# mainboard.net
KiCad netlist of a schematic drawn in EAGLE
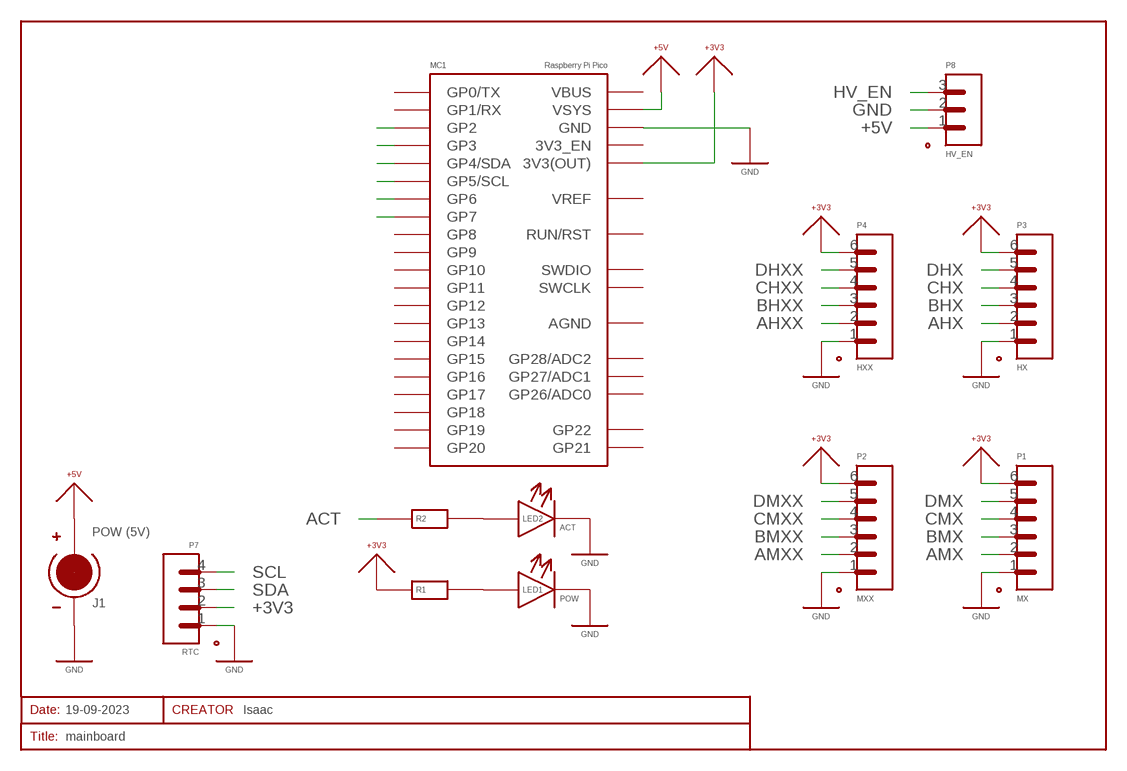
[diagram p0: schematic, sheet 1]

(export (version "E")
  (design (tool "Eeschema 10.0.6"))
  (components
    (comp (ref "CREATOR")
      (value "Isaac")
      (footprint "eagle-import:INFO_T")
      (libsource (lib "eagle-import") (part "INFO_T"))
    )
    (comp (ref "J1")
      (value "POW (5V)")
      (footprint "eagle-import:XH2.54_2-PIN")
      (libsource (lib "eagle-import") (part "DC_POWER_CENTER-POS_XH2.54"))
    )
    (comp (ref "LED1")
      (value "POW")
      (footprint "eagle-import:LED_3MM")
      (libsource (lib "eagle-import") (part "LED_3MM"))
    )
    (comp (ref "LED2")
      (value "ACT")
      (footprint "eagle-import:LED_3MM")
      (libsource (lib "eagle-import") (part "LED_3MM"))
    )
    (comp (ref "MC1")
      (value "RASPBERRY-PI-PICO_THT")
      (footprint "eagle-import:RASPBERRY-PI-PICO_THT")
      (libsource (lib "eagle-import") (part "RASPBERRY-PI-PICO_THT"))
    )
    (comp (ref "P1")
      (value "MX")
      (footprint "eagle-import:XH2.54_6-PIN")
      (libsource (lib "eagle-import") (part "PORT_6-PIN_XH2.54"))
    )
    (comp (ref "P2")
      (value "MXX")
      (footprint "eagle-import:XH2.54_6-PIN")
      (libsource (lib "eagle-import") (part "PORT_6-PIN_XH2.54"))
    )
    (comp (ref "P3")
      (value "HX")
      (footprint "eagle-import:XH2.54_6-PIN")
      (libsource (lib "eagle-import") (part "PORT_6-PIN_XH2.54"))
    )
    (comp (ref "P4")
      (value "HXX")
      (footprint "eagle-import:XH2.54_6-PIN")
      (libsource (lib "eagle-import") (part "PORT_6-PIN_XH2.54"))
    )
    (comp (ref "P7")
      (value "RTC")
      (footprint "eagle-import:XH2.54_4-PIN")
      (libsource (lib "eagle-import") (part "PORT_4-PIN_XH2.54"))
    )
    (comp (ref "P8")
      (value "HV_EN")
      (footprint "eagle-import:XH2.54_3-PIN")
      (libsource (lib "eagle-import") (part "PORT_3-PIN_XH2.54"))
    )
    (comp (ref "R1")
      (value "RESISTOR")
      (footprint "eagle-import:RESISTOR_10.16MM")
      (libsource (lib "eagle-import") (part "RESISTOR"))
    )
    (comp (ref "R2")
      (value "RESISTOR")
      (footprint "eagle-import:RESISTOR_10.16MM")
      (libsource (lib "eagle-import") (part "RESISTOR"))
    )
    (comp (ref "SCHEMATIC1")
      (value "19-09-2023")
      (footprint "eagle-import:SHEET")
      (libsource (lib "eagle-import") (part "SHEET"))
    )
  )
  (nets
    (net (code "1") (name "+3V3") (class "Default")
      (node (ref "MC1") (pin "36") (pinfunction "3V3(OUT)_36") (pintype "power_in"))
      (node (ref "P1") (pin "6") (pinfunction "6_6") (pintype "bidirectional"))
      (node (ref "P2") (pin "6") (pinfunction "6_6") (pintype "bidirectional"))
      (node (ref "P3") (pin "6") (pinfunction "6_6") (pintype "bidirectional"))
      (node (ref "P4") (pin "6") (pinfunction "6_6") (pintype "bidirectional"))
      (node (ref "P7") (pin "2") (pinfunction "2_2") (pintype "bidirectional"))
      (node (ref "R1") (pin "1") (pinfunction "1_1") (pintype "bidirectional"))
    )
    (net (code "2") (name "+5V") (class "Default")
      (node (ref "J1") (pin "2") (pinfunction "+_2") (pintype "output"))
      (node (ref "MC1") (pin "39") (pinfunction "VSYS_39") (pintype "bidirectional"))
      (node (ref "P8") (pin "1") (pinfunction "1_1") (pintype "bidirectional"))
    )
    (net (code "3") (name "/ACT") (class "Default")
      (node (ref "R2") (pin "1") (pinfunction "1_1") (pintype "bidirectional"))
    )
    (net (code "4") (name "/AGND") (class "Default")
      (node (ref "MC1") (pin "33") (pinfunction "AGND_33") (pintype "power_in"))
    )
    (net (code "5") (name "/AHX") (class "Default")
      (node (ref "P3") (pin "2") (pinfunction "2_2") (pintype "bidirectional"))
    )
    (net (code "6") (name "/AHXX") (class "Default")
      (node (ref "P4") (pin "2") (pinfunction "2_2") (pintype "bidirectional"))
    )
    (net (code "7") (name "/AMX") (class "Default")
      (node (ref "P1") (pin "2") (pinfunction "2_2") (pintype "bidirectional"))
    )
    (net (code "8") (name "/AMXX") (class "Default")
      (node (ref "P2") (pin "2") (pinfunction "2_2") (pintype "bidirectional"))
    )
    (net (code "9") (name "/BHX") (class "Default")
      (node (ref "P3") (pin "3") (pinfunction "3_3") (pintype "bidirectional"))
    )
    (net (code "10") (name "/BHXX") (class "Default")
      (node (ref "P4") (pin "3") (pinfunction "3_3") (pintype "bidirectional"))
    )
    (net (code "11") (name "/BMX") (class "Default")
      (node (ref "P1") (pin "3") (pinfunction "3_3") (pintype "bidirectional"))
    )
    (net (code "12") (name "/BMXX") (class "Default")
      (node (ref "P2") (pin "3") (pinfunction "3_3") (pintype "bidirectional"))
    )
    (net (code "13") (name "/CHX") (class "Default")
      (node (ref "P3") (pin "4") (pinfunction "4_4") (pintype "bidirectional"))
    )
    (net (code "14") (name "/CHXX") (class "Default")
      (node (ref "P4") (pin "4") (pinfunction "4_4") (pintype "bidirectional"))
    )
    (net (code "15") (name "/CMX") (class "Default")
      (node (ref "P1") (pin "4") (pinfunction "4_4") (pintype "bidirectional"))
    )
    (net (code "16") (name "/CMXX") (class "Default")
      (node (ref "P2") (pin "4") (pinfunction "4_4") (pintype "bidirectional"))
    )
    (net (code "17") (name "/DHX") (class "Default")
      (node (ref "P3") (pin "5") (pinfunction "5_5") (pintype "bidirectional"))
    )
    (net (code "18") (name "/DHXX") (class "Default")
      (node (ref "P4") (pin "5") (pinfunction "5_5") (pintype "bidirectional"))
    )
    (net (code "19") (name "/DMX") (class "Default")
      (node (ref "P1") (pin "5") (pinfunction "5_5") (pintype "bidirectional"))
    )
    (net (code "20") (name "/DMXX") (class "Default")
      (node (ref "P2") (pin "5") (pinfunction "5_5") (pintype "bidirectional"))
    )
    (net (code "21") (name "/HV_EN") (class "Default")
      (node (ref "P8") (pin "3") (pinfunction "3_3") (pintype "bidirectional"))
    )
    (net (code "22") (name "/SCL") (class "Default")
      (node (ref "P7") (pin "4") (pinfunction "4_4") (pintype "bidirectional"))
    )
    (net (code "23") (name "/SDA") (class "Default")
      (node (ref "P7") (pin "3") (pinfunction "3_3") (pintype "bidirectional"))
    )
    (net (code "24") (name "GND") (class "Default")
      (node (ref "J1") (pin "1") (pinfunction "GND_1") (pintype "power_in"))
      (node (ref "LED1") (pin "-") (pinfunction "-_-") (pintype "output"))
      (node (ref "LED2") (pin "-") (pinfunction "-_-") (pintype "output"))
      (node (ref "MC1") (pin "13") (pinfunction "GND_13") (pintype "power_in"))
      (node (ref "MC1") (pin "18") (pinfunction "GND_18") (pintype "power_in"))
      (node (ref "MC1") (pin "23") (pinfunction "GND_23") (pintype "power_in"))
      (node (ref "MC1") (pin "28") (pinfunction "GND_28") (pintype "power_in"))
      (node (ref "MC1") (pin "3") (pinfunction "GND_3") (pintype "power_in"))
      (node (ref "MC1") (pin "38") (pinfunction "GND_38") (pintype "power_in"))
      (node (ref "MC1") (pin "8") (pinfunction "GND_8") (pintype "power_in"))
      (node (ref "MC1") (pin "D_GND") (pinfunction "GND_D_GND") (pintype "power_in"))
      (node (ref "P1") (pin "1") (pinfunction "1_1") (pintype "bidirectional"))
      (node (ref "P2") (pin "1") (pinfunction "1_1") (pintype "bidirectional"))
      (node (ref "P3") (pin "1") (pinfunction "1_1") (pintype "bidirectional"))
      (node (ref "P4") (pin "1") (pinfunction "1_1") (pintype "bidirectional"))
      (node (ref "P7") (pin "1") (pinfunction "1_1") (pintype "bidirectional"))
      (node (ref "P8") (pin "2") (pinfunction "2_2") (pintype "bidirectional"))
    )
    (net (code "25") (name "Net-(LED1-Pad+)") (class "Default")
      (node (ref "LED1") (pin "+") (pinfunction "+_+") (pintype "input"))
      (node (ref "R1") (pin "2") (pinfunction "2_2") (pintype "bidirectional"))
    )
    (net (code "26") (name "Net-(LED2-Pad+)") (class "Default")
      (node (ref "LED2") (pin "+") (pinfunction "+_+") (pintype "input"))
      (node (ref "R2") (pin "2") (pinfunction "2_2") (pintype "bidirectional"))
    )
    (net (code "27") (name "unconnected-(MC1-3V3_EN-Pad37)") (class "Default")
      (node (ref "MC1") (pin "37") (pinfunction "3V3_EN_37") (pintype "bidirectional"))
    )
    (net (code "28") (name "unconnected-(MC1-GP0{slash}TX-Pad1)") (class "Default")
      (node (ref "MC1") (pin "1") (pinfunction "GP0/TX_1") (pintype "bidirectional"))
    )
    (net (code "29") (name "unconnected-(MC1-GP1{slash}RX-Pad2)") (class "Default")
      (node (ref "MC1") (pin "2") (pinfunction "GP1/RX_2") (pintype "bidirectional"))
    )
    (net (code "30") (name "unconnected-(MC1-GP2-Pad4)") (class "Default")
      (node (ref "MC1") (pin "4") (pinfunction "GP2_4") (pintype "bidirectional"))
    )
    (net (code "31") (name "unconnected-(MC1-GP3-Pad5)") (class "Default")
      (node (ref "MC1") (pin "5") (pinfunction "GP3_5") (pintype "bidirectional"))
    )
    (net (code "32") (name "unconnected-(MC1-GP4{slash}SDA-Pad6)") (class "Default")
      (node (ref "MC1") (pin "6") (pinfunction "GP4/SDA_6") (pintype "bidirectional"))
    )
    (net (code "33") (name "unconnected-(MC1-GP5{slash}SCL-Pad7)") (class "Default")
      (node (ref "MC1") (pin "7") (pinfunction "GP5/SCL_7") (pintype "bidirectional"))
    )
    (net (code "34") (name "unconnected-(MC1-GP6-Pad9)") (class "Default")
      (node (ref "MC1") (pin "9") (pinfunction "GP6_9") (pintype "bidirectional"))
    )
    (net (code "35") (name "unconnected-(MC1-GP7-Pad10)") (class "Default")
      (node (ref "MC1") (pin "10") (pinfunction "GP7_10") (pintype "bidirectional"))
    )
    (net (code "36") (name "unconnected-(MC1-GP8-Pad11)") (class "Default")
      (node (ref "MC1") (pin "11") (pinfunction "GP8_11") (pintype "bidirectional"))
    )
    (net (code "37") (name "unconnected-(MC1-GP9-Pad12)") (class "Default")
      (node (ref "MC1") (pin "12") (pinfunction "GP9_12") (pintype "bidirectional"))
    )
    (net (code "38") (name "unconnected-(MC1-GP10-Pad14)") (class "Default")
      (node (ref "MC1") (pin "14") (pinfunction "GP10_14") (pintype "bidirectional"))
    )
    (net (code "39") (name "unconnected-(MC1-GP11-Pad15)") (class "Default")
      (node (ref "MC1") (pin "15") (pinfunction "GP11_15") (pintype "bidirectional"))
    )
    (net (code "40") (name "unconnected-(MC1-GP12-Pad16)") (class "Default")
      (node (ref "MC1") (pin "16") (pinfunction "GP12_16") (pintype "bidirectional"))
    )
    (net (code "41") (name "unconnected-(MC1-GP13-Pad17)") (class "Default")
      (node (ref "MC1") (pin "17") (pinfunction "GP13_17") (pintype "bidirectional"))
    )
    (net (code "42") (name "unconnected-(MC1-GP14-Pad19)") (class "Default")
      (node (ref "MC1") (pin "19") (pinfunction "GP14_19") (pintype "bidirectional"))
    )
    (net (code "43") (name "unconnected-(MC1-GP15-Pad20)") (class "Default")
      (node (ref "MC1") (pin "20") (pinfunction "GP15_20") (pintype "bidirectional"))
    )
    (net (code "44") (name "unconnected-(MC1-GP16-Pad21)") (class "Default")
      (node (ref "MC1") (pin "21") (pinfunction "GP16_21") (pintype "bidirectional"))
    )
    (net (code "45") (name "unconnected-(MC1-GP17-Pad22)") (class "Default")
      (node (ref "MC1") (pin "22") (pinfunction "GP17_22") (pintype "bidirectional"))
    )
    (net (code "46") (name "unconnected-(MC1-GP18-Pad24)") (class "Default")
      (node (ref "MC1") (pin "24") (pinfunction "GP18_24") (pintype "bidirectional"))
    )
    (net (code "47") (name "unconnected-(MC1-GP19-Pad25)") (class "Default")
      (node (ref "MC1") (pin "25") (pinfunction "GP19_25") (pintype "bidirectional"))
    )
    (net (code "48") (name "unconnected-(MC1-GP20-Pad26)") (class "Default")
      (node (ref "MC1") (pin "26") (pinfunction "GP20_26") (pintype "bidirectional"))
    )
    (net (code "49") (name "unconnected-(MC1-GP21-Pad27)") (class "Default")
      (node (ref "MC1") (pin "27") (pinfunction "GP21_27") (pintype "bidirectional"))
    )
    (net (code "50") (name "unconnected-(MC1-GP22-Pad29)") (class "Default")
      (node (ref "MC1") (pin "29") (pinfunction "GP22_29") (pintype "bidirectional"))
    )
    (net (code "51") (name "unconnected-(MC1-GP26{slash}ADC0-Pad31)") (class "Default")
      (node (ref "MC1") (pin "31") (pinfunction "GP26/ADC0_31") (pintype "bidirectional"))
    )
    (net (code "52") (name "unconnected-(MC1-GP27{slash}ADC1-Pad32)") (class "Default")
      (node (ref "MC1") (pin "32") (pinfunction "GP27/ADC1_32") (pintype "bidirectional"))
    )
    (net (code "53") (name "unconnected-(MC1-GP28{slash}ADC2-Pad34)") (class "Default")
      (node (ref "MC1") (pin "34") (pinfunction "GP28/ADC2_34") (pintype "bidirectional"))
    )
    (net (code "54") (name "unconnected-(MC1-PadSWCLK)") (class "Default")
      (node (ref "MC1") (pin "SWCLK") (pinfunction "SWCLK_SWCLK") (pintype "bidirectional"))
    )
    (net (code "55") (name "unconnected-(MC1-PadSWDIO)") (class "Default")
      (node (ref "MC1") (pin "SWDIO") (pinfunction "SWDIO_SWDIO") (pintype "bidirectional"))
    )
    (net (code "56") (name "unconnected-(MC1-RUN{slash}RST-Pad30)") (class "Default")
      (node (ref "MC1") (pin "30") (pinfunction "RUN/RST_30") (pintype "bidirectional"))
    )
    (net (code "57") (name "unconnected-(MC1-VBUS-Pad40)") (class "Default")
      (node (ref "MC1") (pin "40") (pinfunction "VBUS_40") (pintype "bidirectional"))
    )
    (net (code "58") (name "unconnected-(MC1-VREF-Pad35)") (class "Default")
      (node (ref "MC1") (pin "35") (pinfunction "VREF_35") (pintype "bidirectional"))
    )
  )
)
